# EA3036C.net
KiCad netlist of a schematic drawn in Altium Designer
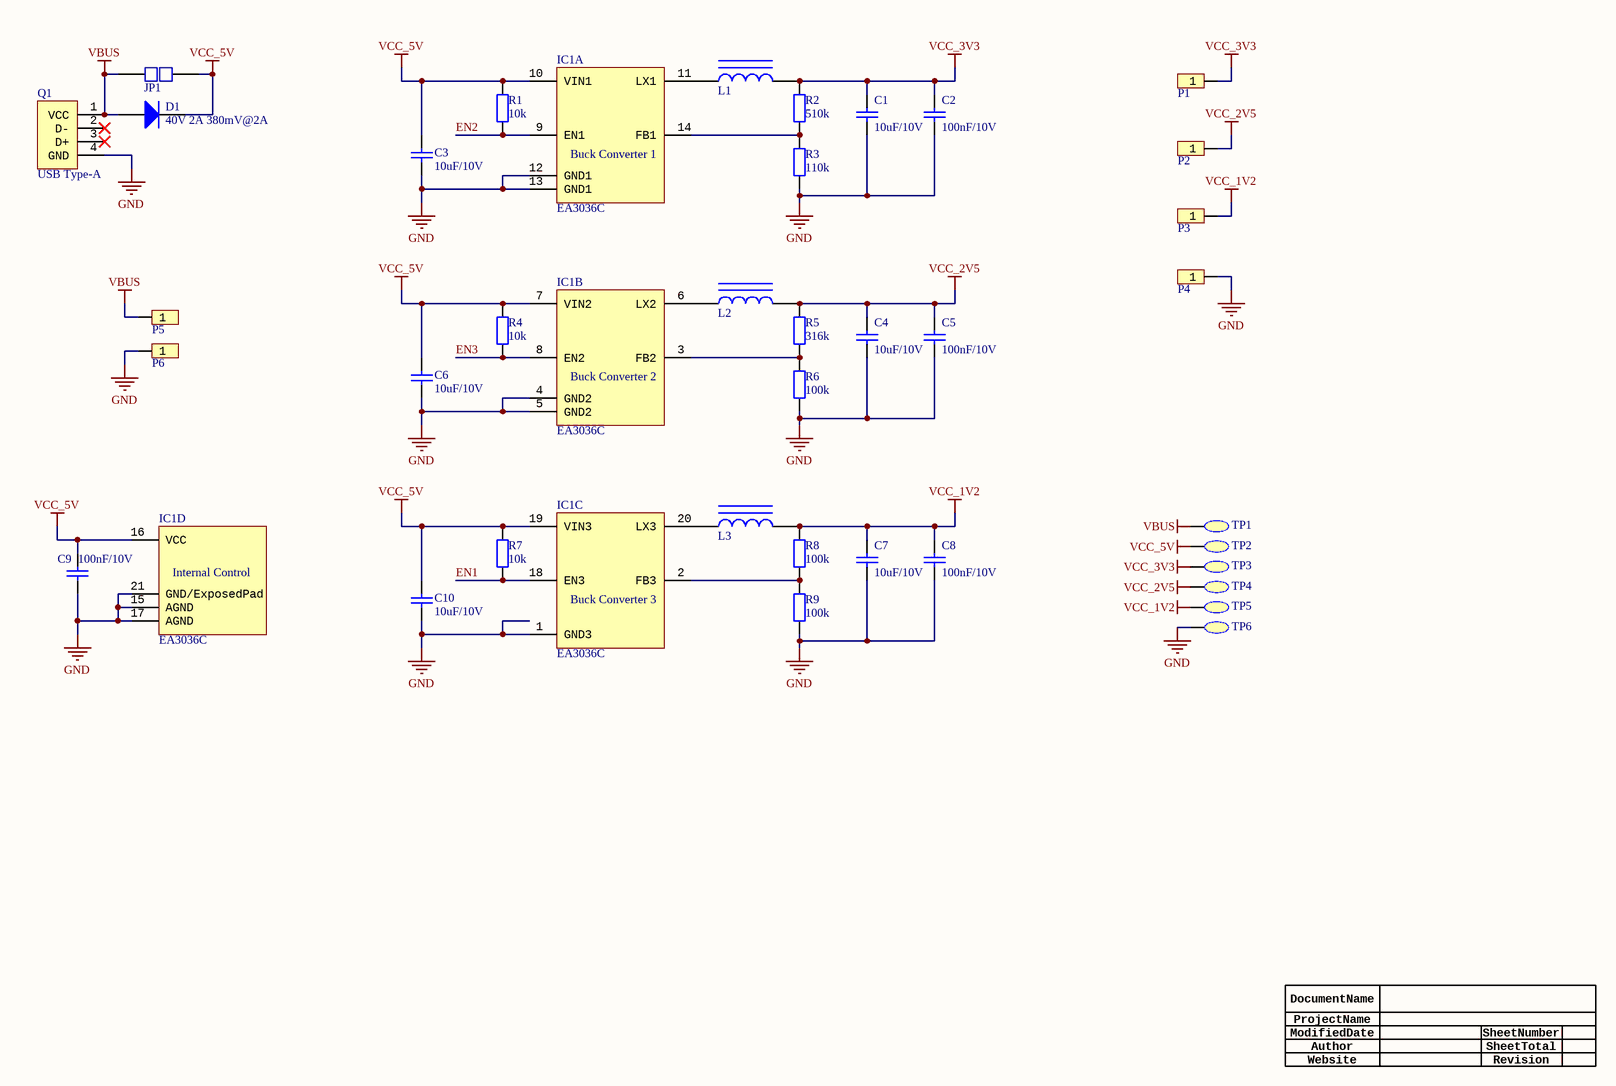
[diagram p0: EA3036C.SchDoc]

(export (version "E")
  (design (tool "Eeschema 10.0.6"))
  (components
    (comp (ref "C1")
      (value "10uF/10V")
      (footprint "CAP-0402")
      (description "CC0402MRX5R6BB106(±20%)")
      (libsource (lib "Power_Lib_Altium") (part "CAP"))
    )
    (comp (ref "C2")
      (value "100nF/10V")
      (footprint "CAP-0402")
      (description "CC0402KRX5R6BB104(±10%)")
      (libsource (lib "Power_Lib_Altium") (part "CAP"))
    )
    (comp (ref "C3")
      (value "10uF/10V")
      (footprint "CAP-0402")
      (description "CC0402MRX5R6BB106(±20%)")
      (libsource (lib "Power_Lib_Altium") (part "CAP"))
    )
    (comp (ref "C4")
      (value "10uF/10V")
      (footprint "CAP-0402")
      (description "CC0402MRX5R6BB106(±20%)")
      (libsource (lib "Power_Lib_Altium") (part "CAP"))
    )
    (comp (ref "C5")
      (value "100nF/10V")
      (footprint "CAP-0402")
      (description "CC0402KRX5R6BB104(±10%)")
      (libsource (lib "Power_Lib_Altium") (part "CAP"))
    )
    (comp (ref "C6")
      (value "10uF/10V")
      (footprint "CAP-0402")
      (description "CC0402MRX5R6BB106(±20%)")
      (libsource (lib "Power_Lib_Altium") (part "CAP"))
    )
    (comp (ref "C7")
      (value "10uF/10V")
      (footprint "CAP-0402")
      (description "CC0402MRX5R6BB106(±20%)")
      (libsource (lib "Power_Lib_Altium") (part "CAP"))
    )
    (comp (ref "C8")
      (value "100nF/10V")
      (footprint "CAP-0402")
      (description "CC0402KRX5R6BB104(±10%)")
      (libsource (lib "Power_Lib_Altium") (part "CAP"))
    )
    (comp (ref "C9")
      (value "100nF/10V")
      (footprint "CAP-0402")
      (description "CC0402KRX5R6BB104(±10%)")
      (libsource (lib "Power_Lib_Altium") (part "CAP"))
    )
    (comp (ref "C10")
      (value "10uF/10V")
      (footprint "CAP-0402")
      (description "CC0402MRX5R6BB106(±20%)")
      (libsource (lib "Power_Lib_Altium") (part "CAP"))
    )
    (comp (ref "D1")
      (value "40V 2A 380mV@2A")
      (footprint "SOD_123")
      (description "PSBD1DF40V2L")
      (libsource (lib "Power_Lib_Altium") (part "DIODE"))
    )
    (comp (ref "IC1")
      (value "EA3036C")
      (footprint "QFN3mmx3mm-20")
      (libsource (lib "Power_Lib_Altium") (part "EA3036C"))
    )
    (comp (ref "JP1")
      (value "Select")
      (footprint "选择焊点-0402")
      (description "选择焊点")
      (libsource (lib "Power_Lib_Altium") (part "Select"))
    )
    (comp (ref "L1")
      (value "10uH")
      (footprint "L-2520")
      (description "电感")
      (libsource (lib "Power_Lib_Altium") (part "INDUCTOR"))
    )
    (comp (ref "L2")
      (value "10uH")
      (footprint "L-2520")
      (description "电感")
      (libsource (lib "Power_Lib_Altium") (part "INDUCTOR"))
    )
    (comp (ref "L3")
      (value "10uH")
      (footprint "L-2520")
      (description "电感")
      (libsource (lib "Power_Lib_Altium") (part "INDUCTOR"))
    )
    (comp (ref "P1")
      (value "HDR1x2_2.54")
      (footprint "HDR1X1_2.54")
      (description "Header")
      (libsource (lib "Power_Lib_Altium") (part "HDR1x1_2.54"))
    )
    (comp (ref "P2")
      (value "HDR1x2_2.54")
      (footprint "HDR1X1_2.54")
      (description "Header")
      (libsource (lib "Power_Lib_Altium") (part "HDR1x1_2.54"))
    )
    (comp (ref "P3")
      (value "HDR1x2_2.54")
      (footprint "HDR1X1_2.54")
      (description "Header")
      (libsource (lib "Power_Lib_Altium") (part "HDR1x1_2.54"))
    )
    (comp (ref "P4")
      (value "HDR1x2_2.54")
      (footprint "HDR1X1_2.54")
      (description "Header")
      (libsource (lib "Power_Lib_Altium") (part "HDR1x1_2.54"))
    )
    (comp (ref "P5")
      (value "HDR1x2_2.54")
      (footprint "HDR1X1_2.54")
      (description "Header")
      (libsource (lib "") (part "HDR1x1_2.54_1"))
    )
    (comp (ref "P6")
      (value "HDR1x2_2.54")
      (footprint "HDR1X1_2.54")
      (description "Header")
      (libsource (lib "") (part "HDR1x1_2.54_1"))
    )
    (comp (ref "Q1")
      (value "USB Type-A")
      (footprint "USB-A-male")
      (description "U217-041N-4BV81")
      (libsource (lib "Power_Lib_Altium") (part "USB A"))
    )
    (comp (ref "R1")
      (value "10k")
      (footprint "R-0402")
      (description "RC0402FR-0710KL")
      (libsource (lib "Power_Lib_Altium") (part "RES"))
    )
    (comp (ref "R2")
      (value "510k")
      (footprint "R-0402")
      (description "RC0402FR-07510KL")
      (libsource (lib "Power_Lib_Altium") (part "RES"))
    )
    (comp (ref "R3")
      (value "110k")
      (footprint "R-0402")
      (description "RC0402FR-07510KL")
      (libsource (lib "Power_Lib_Altium") (part "RES"))
    )
    (comp (ref "R4")
      (value "10k")
      (footprint "R-0402")
      (description "RC0402FR-0710KL")
      (libsource (lib "Power_Lib_Altium") (part "RES"))
    )
    (comp (ref "R5")
      (value "316k")
      (footprint "R-0402")
      (description "RC0402FR-07316KL")
      (libsource (lib "Power_Lib_Altium") (part "RES"))
    )
    (comp (ref "R6")
      (value "100k")
      (footprint "R-0402")
      (description "RC0402FR-07100KL")
      (libsource (lib "Power_Lib_Altium") (part "RES"))
    )
    (comp (ref "R7")
      (value "10k")
      (footprint "R-0402")
      (description "RC0402FR-0710KL")
      (libsource (lib "Power_Lib_Altium") (part "RES"))
    )
    (comp (ref "R8")
      (value "100k")
      (footprint "R-0402")
      (description "RC0402FR-07100KL")
      (libsource (lib "Power_Lib_Altium") (part "RES"))
    )
    (comp (ref "R9")
      (value "100k")
      (footprint "R-0402")
      (description "RC0402FR-07100KL")
      (libsource (lib "Power_Lib_Altium") (part "RES"))
    )
    (comp (ref "TP1")
      (value "TestPoint")
      (footprint "TestPoint")
      (description "测试点")
      (libsource (lib "Power_Lib_Altium") (part "TestPoint"))
    )
    (comp (ref "TP2")
      (value "TestPoint")
      (footprint "TestPoint")
      (description "测试点")
      (libsource (lib "Power_Lib_Altium") (part "TestPoint"))
    )
    (comp (ref "TP3")
      (value "TestPoint")
      (footprint "TestPoint")
      (description "测试点")
      (libsource (lib "Power_Lib_Altium") (part "TestPoint"))
    )
    (comp (ref "TP4")
      (value "TestPoint")
      (footprint "TestPoint")
      (description "测试点")
      (libsource (lib "Power_Lib_Altium") (part "TestPoint"))
    )
    (comp (ref "TP5")
      (value "TestPoint")
      (footprint "TestPoint")
      (description "测试点")
      (libsource (lib "Power_Lib_Altium") (part "TestPoint"))
    )
    (comp (ref "TP6")
      (value "TestPoint")
      (footprint "TestPoint")
      (description "测试点")
      (libsource (lib "Power_Lib_Altium") (part "TestPoint"))
    )
  )
  (nets
    (net (code "1") (name "/EN1") (class "Default")
      (node (ref "IC1") (pin "18") (pinfunction "EN3_18") (pintype "passive"))
      (node (ref "R7") (pin "1") (pinfunction "1_1") (pintype "passive"))
    )
    (net (code "2") (name "/EN2") (class "Default")
      (node (ref "IC1") (pin "9") (pinfunction "EN1_9") (pintype "passive"))
      (node (ref "R1") (pin "1") (pinfunction "1_1") (pintype "passive"))
    )
    (net (code "3") (name "/EN3") (class "Default")
      (node (ref "IC1") (pin "8") (pinfunction "EN2_8") (pintype "passive"))
      (node (ref "R4") (pin "1") (pinfunction "1_1") (pintype "passive"))
    )
    (net (code "4") (name "GND") (class "Default")
      (node (ref "C1") (pin "1") (pinfunction "1_1") (pintype "passive"))
      (node (ref "C10") (pin "1") (pinfunction "1_1") (pintype "passive"))
      (node (ref "C2") (pin "1") (pinfunction "1_1") (pintype "passive"))
      (node (ref "C3") (pin "1") (pinfunction "1_1") (pintype "passive"))
      (node (ref "C4") (pin "1") (pinfunction "1_1") (pintype "passive"))
      (node (ref "C5") (pin "1") (pinfunction "1_1") (pintype "passive"))
      (node (ref "C6") (pin "1") (pinfunction "1_1") (pintype "passive"))
      (node (ref "C7") (pin "1") (pinfunction "1_1") (pintype "passive"))
      (node (ref "C8") (pin "1") (pinfunction "1_1") (pintype "passive"))
      (node (ref "C9") (pin "1") (pinfunction "1_1") (pintype "passive"))
      (node (ref "IC1") (pin "1") (pinfunction "GND3_1") (pintype "power_in"))
      (node (ref "IC1") (pin "12") (pinfunction "GND1_12") (pintype "power_in"))
      (node (ref "IC1") (pin "13") (pinfunction "GND1_13") (pintype "power_in"))
      (node (ref "IC1") (pin "15") (pinfunction "AGND_15") (pintype "power_in"))
      (node (ref "IC1") (pin "17") (pinfunction "AGND_17") (pintype "power_in"))
      (node (ref "IC1") (pin "21") (pinfunction "GND/ExposedPad_21") (pintype "power_in"))
      (node (ref "IC1") (pin "4") (pinfunction "GND2_4") (pintype "power_in"))
      (node (ref "IC1") (pin "5") (pinfunction "GND2_5") (pintype "power_in"))
      (node (ref "P4") (pin "1") (pinfunction "1_1") (pintype "passive"))
      (node (ref "P6") (pin "1") (pinfunction "1_1") (pintype "passive"))
      (node (ref "Q1") (pin "4") (pinfunction "GND_4") (pintype "passive"))
      (node (ref "R3") (pin "1") (pinfunction "1_1") (pintype "passive"))
      (node (ref "R6") (pin "1") (pinfunction "1_1") (pintype "passive"))
      (node (ref "R9") (pin "1") (pinfunction "1_1") (pintype "passive"))
      (node (ref "TP6") (pin "1") (pinfunction "1_1") (pintype "passive"))
    )
    (net (code "5") (name "Net-(IC1A-FB1)") (class "Default")
      (node (ref "IC1") (pin "14") (pinfunction "FB1_14") (pintype "passive"))
      (node (ref "R2") (pin "1") (pinfunction "1_1") (pintype "passive"))
      (node (ref "R3") (pin "2") (pinfunction "2_2") (pintype "passive"))
    )
    (net (code "6") (name "Net-(IC1A-LX1)") (class "Default")
      (node (ref "IC1") (pin "11") (pinfunction "LX1_11") (pintype "passive"))
      (node (ref "L1") (pin "1") (pinfunction "1_1") (pintype "passive"))
    )
    (net (code "7") (name "Net-(IC1B-FB2)") (class "Default")
      (node (ref "IC1") (pin "3") (pinfunction "FB2_3") (pintype "passive"))
      (node (ref "R5") (pin "1") (pinfunction "1_1") (pintype "passive"))
      (node (ref "R6") (pin "2") (pinfunction "2_2") (pintype "passive"))
    )
    (net (code "8") (name "Net-(IC1B-LX2)") (class "Default")
      (node (ref "IC1") (pin "6") (pinfunction "LX2_6") (pintype "passive"))
      (node (ref "L2") (pin "1") (pinfunction "1_1") (pintype "passive"))
    )
    (net (code "9") (name "Net-(IC1C-FB3)") (class "Default")
      (node (ref "IC1") (pin "2") (pinfunction "FB3_2") (pintype "passive"))
      (node (ref "R8") (pin "1") (pinfunction "1_1") (pintype "passive"))
      (node (ref "R9") (pin "2") (pinfunction "2_2") (pintype "passive"))
    )
    (net (code "10") (name "Net-(IC1C-LX3)") (class "Default")
      (node (ref "IC1") (pin "20") (pinfunction "LX3_20") (pintype "passive"))
      (node (ref "L3") (pin "1") (pinfunction "1_1") (pintype "passive"))
    )
    (net (code "11") (name "VBUS") (class "Default")
      (node (ref "D1") (pin "1") (pinfunction "A_1") (pintype "passive"))
      (node (ref "JP1") (pin "1") (pinfunction "1_1") (pintype "passive"))
      (node (ref "P5") (pin "1") (pinfunction "1_1") (pintype "passive"))
      (node (ref "Q1") (pin "1") (pinfunction "VCC_1") (pintype "passive"))
      (node (ref "TP1") (pin "1") (pinfunction "1_1") (pintype "passive"))
    )
    (net (code "12") (name "VCC_1V2") (class "Default")
      (node (ref "C7") (pin "2") (pinfunction "2_2") (pintype "passive"))
      (node (ref "C8") (pin "2") (pinfunction "2_2") (pintype "passive"))
      (node (ref "L3") (pin "2") (pinfunction "2_2") (pintype "passive"))
      (node (ref "P3") (pin "1") (pinfunction "1_1") (pintype "passive"))
      (node (ref "R8") (pin "2") (pinfunction "2_2") (pintype "passive"))
      (node (ref "TP5") (pin "1") (pinfunction "1_1") (pintype "passive"))
    )
    (net (code "13") (name "VCC_2V5") (class "Default")
      (node (ref "C4") (pin "2") (pinfunction "2_2") (pintype "passive"))
      (node (ref "C5") (pin "2") (pinfunction "2_2") (pintype "passive"))
      (node (ref "L2") (pin "2") (pinfunction "2_2") (pintype "passive"))
      (node (ref "P2") (pin "1") (pinfunction "1_1") (pintype "passive"))
      (node (ref "R5") (pin "2") (pinfunction "2_2") (pintype "passive"))
      (node (ref "TP4") (pin "1") (pinfunction "1_1") (pintype "passive"))
    )
    (net (code "14") (name "VCC_3V3") (class "Default")
      (node (ref "C1") (pin "2") (pinfunction "2_2") (pintype "passive"))
      (node (ref "C2") (pin "2") (pinfunction "2_2") (pintype "passive"))
      (node (ref "L1") (pin "2") (pinfunction "2_2") (pintype "passive"))
      (node (ref "P1") (pin "1") (pinfunction "1_1") (pintype "passive"))
      (node (ref "R2") (pin "2") (pinfunction "2_2") (pintype "passive"))
      (node (ref "TP3") (pin "1") (pinfunction "1_1") (pintype "passive"))
    )
    (net (code "15") (name "VCC_5V") (class "Default")
      (node (ref "C10") (pin "2") (pinfunction "2_2") (pintype "passive"))
      (node (ref "C3") (pin "2") (pinfunction "2_2") (pintype "passive"))
      (node (ref "C6") (pin "2") (pinfunction "2_2") (pintype "passive"))
      (node (ref "C9") (pin "2") (pinfunction "2_2") (pintype "passive"))
      (node (ref "D1") (pin "2") (pinfunction "K_2") (pintype "passive"))
      (node (ref "IC1") (pin "10") (pinfunction "VIN1_10") (pintype "power_in"))
      (node (ref "IC1") (pin "16") (pinfunction "VCC_16") (pintype "power_in"))
      (node (ref "IC1") (pin "19") (pinfunction "VIN3_19") (pintype "power_in"))
      (node (ref "IC1") (pin "7") (pinfunction "VIN2_7") (pintype "power_in"))
      (node (ref "JP1") (pin "2") (pinfunction "2_2") (pintype "passive"))
      (node (ref "R1") (pin "2") (pinfunction "2_2") (pintype "passive"))
      (node (ref "R4") (pin "2") (pinfunction "2_2") (pintype "passive"))
      (node (ref "R7") (pin "2") (pinfunction "2_2") (pintype "passive"))
      (node (ref "TP2") (pin "1") (pinfunction "1_1") (pintype "passive"))
    )
    (net (code "16") (name "unconnected-(Q1-D+-Pad3)") (class "Default")
      (node (ref "Q1") (pin "3") (pinfunction "D+_3") (pintype "passive+no_connect"))
    )
    (net (code "17") (name "unconnected-(Q1-D--Pad2)") (class "Default")
      (node (ref "Q1") (pin "2") (pinfunction "D-_2") (pintype "passive+no_connect"))
    )
  )
)
